# untitled.net
KiCad netlist of a schematic drawn in EAGLE
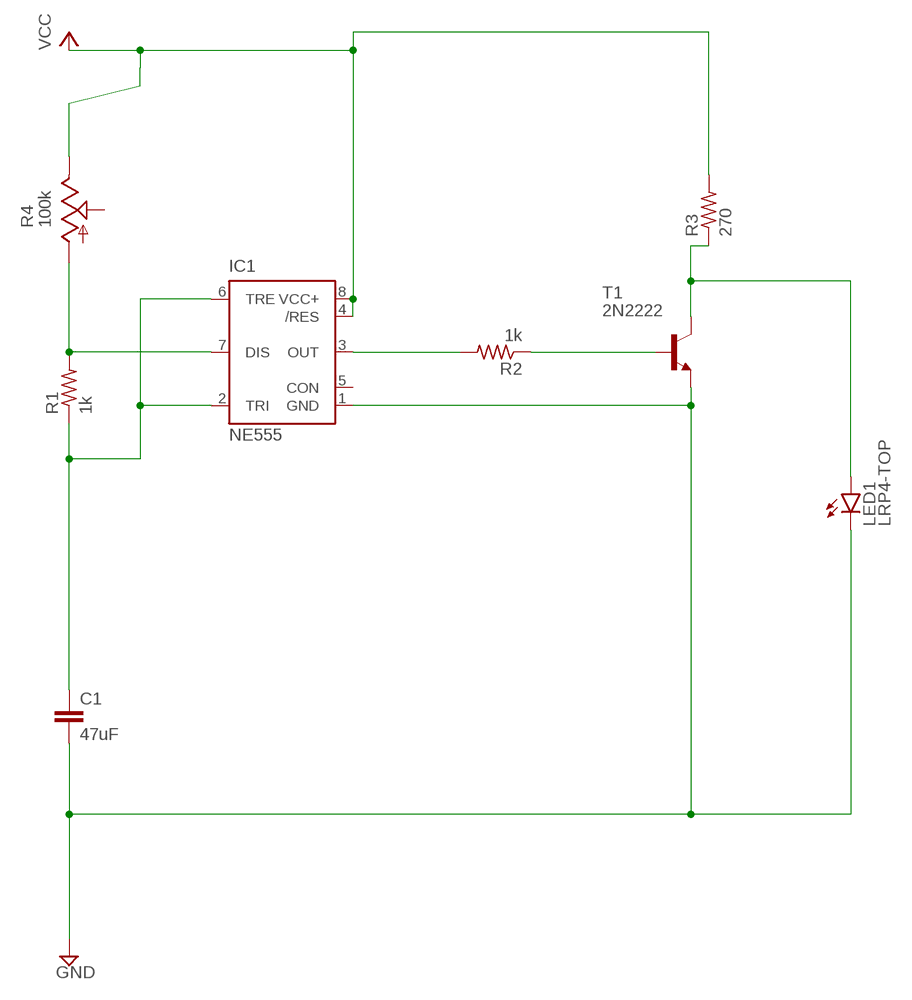
[diagram p0: schematic, sheet 1]

(export (version "E")
  (design (tool "Eeschema 10.0.6"))
  (components
    (comp (ref "C1")
      (value "47uF")
      (footprint "eagle-import:C050-035X075")
      (libsource (lib "eagle-import") (part "C-EU050-035X075"))
    )
    (comp (ref "IC1")
      (value "NE555")
      (footprint "eagle-import:DIL-08")
      (fields (field (name "MF") "Arrow Electronics") (field (name "MPN") "NE555N"))
      (libsource (lib "eagle-import") (part "NE555"))
    )
    (comp (ref "LED1")
      (value "LRP4-TOP")
      (footprint "eagle-import:P47F-TOP")
      (libsource (lib "eagle-import") (part "P4-TOPLR"))
    )
    (comp (ref "R1")
      (value "1k")
      (footprint "eagle-import:0204_5")
      (libsource (lib "eagle-import") (part "R-US_0204/5"))
    )
    (comp (ref "R2")
      (value "1k")
      (footprint "eagle-import:0204_5")
      (libsource (lib "eagle-import") (part "R-US_0204/5"))
    )
    (comp (ref "R3")
      (value "270")
      (footprint "eagle-import:0204_5")
      (libsource (lib "eagle-import") (part "R-US_0204/5"))
    )
    (comp (ref "R4")
      (value "100k")
      (footprint "eagle-import:RJ6S")
      (libsource (lib "eagle-import") (part "TRIM_US-RJ6S"))
    )
    (comp (ref "T1")
      (value "2N2222")
      (footprint "eagle-import:TO18")
      (libsource (lib "eagle-import") (part "2N2222"))
    )
  )
  (nets
    (net (code "1") (name "GND") (class "Default")
      (node (ref "C1") (pin "2") (pinfunction "2_2") (pintype "passive"))
      (node (ref "IC1") (pin "1") (pinfunction "GND_1") (pintype "power_in"))
      (node (ref "LED1") (pin "C") (pinfunction "C_C") (pintype "passive"))
      (node (ref "T1") (pin "1") (pinfunction "E_1") (pintype "passive"))
    )
    (net (code "2") (name "Net-(IC1-DIS)") (class "Default")
      (node (ref "IC1") (pin "7") (pinfunction "DIS_7") (pintype "input"))
      (node (ref "R1") (pin "2") (pinfunction "2_2") (pintype "passive"))
      (node (ref "R4") (pin "A") (pinfunction "A_A") (pintype "passive"))
    )
    (net (code "3") (name "Net-(IC1-OUT)") (class "Default")
      (node (ref "IC1") (pin "3") (pinfunction "OUT_3") (pintype "output"))
      (node (ref "R2") (pin "2") (pinfunction "2_2") (pintype "passive"))
    )
    (net (code "4") (name "Net-(IC1-TRE)") (class "Default")
      (node (ref "C1") (pin "1") (pinfunction "1_1") (pintype "passive"))
      (node (ref "IC1") (pin "2") (pinfunction "TRI_2") (pintype "input"))
      (node (ref "IC1") (pin "6") (pinfunction "TRE_6") (pintype "input"))
      (node (ref "R1") (pin "1") (pinfunction "1_1") (pintype "passive"))
    )
    (net (code "5") (name "Net-(T1-B)") (class "Default")
      (node (ref "R2") (pin "1") (pinfunction "1_1") (pintype "passive"))
      (node (ref "T1") (pin "2") (pinfunction "B_2") (pintype "passive"))
    )
    (net (code "6") (name "Net-(T1-C)") (class "Default")
      (node (ref "LED1") (pin "A") (pinfunction "A_A") (pintype "passive"))
      (node (ref "R3") (pin "1") (pinfunction "1_1") (pintype "passive"))
      (node (ref "T1") (pin "3") (pinfunction "C_3") (pintype "passive"))
    )
    (net (code "7") (name "VCC") (class "Default")
      (node (ref "IC1") (pin "4") (pinfunction "/RES_4") (pintype "input"))
      (node (ref "IC1") (pin "8") (pinfunction "VCC+_8") (pintype "power_in"))
      (node (ref "R3") (pin "2") (pinfunction "2_2") (pintype "passive"))
      (node (ref "R4") (pin "E") (pinfunction "E_E") (pintype "passive"))
    )
    (net (code "8") (name "unconnected-(IC1-CON-Pad5)") (class "Default")
      (node (ref "IC1") (pin "5") (pinfunction "CON_5") (pintype "input"))
    )
    (net (code "9") (name "unconnected-(R4-PadS)") (class "Default")
      (node (ref "R4") (pin "S") (pinfunction "S_S") (pintype "passive"))
    )
  )
)
